# PCB_for_Car.net
KiCad netlist of a schematic drawn in EAGLE
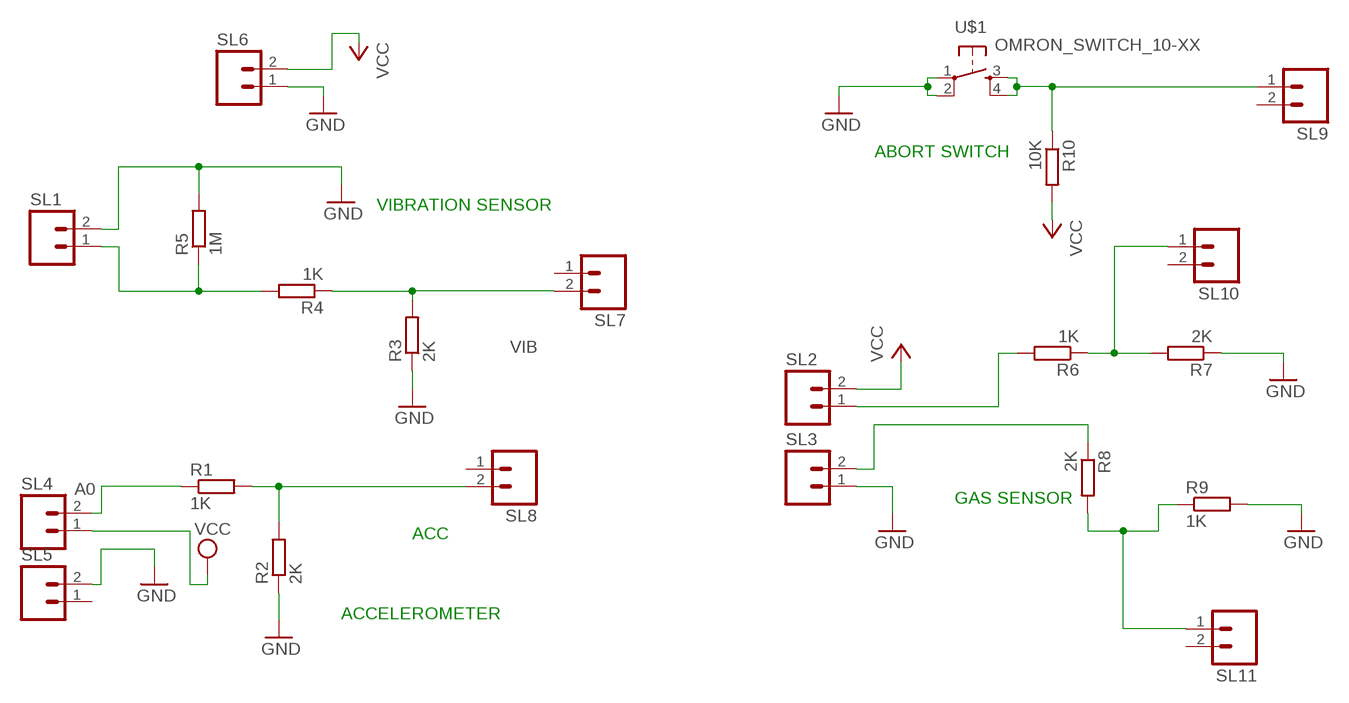
[diagram p0: schematic, sheet 1]

(export (version "E")
  (design (tool "Eeschema 10.0.6"))
  (components
    (comp (ref "R1")
      (value "1K")
      (footprint "eagle-import:0204_7")
      (libsource (lib "eagle-import") (part "R-EU_0204/7"))
    )
    (comp (ref "R2")
      (value "2K")
      (footprint "eagle-import:0204_7")
      (libsource (lib "eagle-import") (part "R-EU_0204/7"))
    )
    (comp (ref "R3")
      (value "2K")
      (footprint "eagle-import:0204_7")
      (libsource (lib "eagle-import") (part "R-EU_0204/7"))
    )
    (comp (ref "R4")
      (value "1K")
      (footprint "eagle-import:0204_7")
      (libsource (lib "eagle-import") (part "R-EU_0204/7"))
    )
    (comp (ref "R5")
      (value "1M")
      (footprint "eagle-import:0204_7")
      (libsource (lib "eagle-import") (part "R-EU_0204/7"))
    )
    (comp (ref "R6")
      (value "1K")
      (footprint "eagle-import:0204_7")
      (libsource (lib "eagle-import") (part "R-EU_0204/7"))
    )
    (comp (ref "R7")
      (value "2K")
      (footprint "eagle-import:0204_7")
      (libsource (lib "eagle-import") (part "R-EU_0204/7"))
    )
    (comp (ref "R8")
      (value "2K")
      (footprint "eagle-import:0204_7")
      (libsource (lib "eagle-import") (part "R-EU_0204/7"))
    )
    (comp (ref "R9")
      (value "1K")
      (footprint "eagle-import:0204_7")
      (libsource (lib "eagle-import") (part "R-EU_0204/7"))
    )
    (comp (ref "R10")
      (value "10K")
      (footprint "eagle-import:0204_7")
      (libsource (lib "eagle-import") (part "R-EU_0204/7"))
    )
    (comp (ref "SL1")
      (value "M02")
      (footprint "eagle-import:02P")
      (libsource (lib "eagle-import") (part "M02"))
    )
    (comp (ref "SL2")
      (value "M02")
      (footprint "eagle-import:02P")
      (libsource (lib "eagle-import") (part "M02"))
    )
    (comp (ref "SL3")
      (value "M02")
      (footprint "eagle-import:02P")
      (libsource (lib "eagle-import") (part "M02"))
    )
    (comp (ref "SL4")
      (value "M02")
      (footprint "eagle-import:02P")
      (libsource (lib "eagle-import") (part "M02"))
    )
    (comp (ref "SL5")
      (value "M02")
      (footprint "eagle-import:02P")
      (libsource (lib "eagle-import") (part "M02"))
    )
    (comp (ref "SL6")
      (value "M02")
      (footprint "eagle-import:02P")
      (libsource (lib "eagle-import") (part "M02"))
    )
    (comp (ref "SL7")
      (value "M02")
      (footprint "eagle-import:02P")
      (libsource (lib "eagle-import") (part "M02"))
    )
    (comp (ref "SL8")
      (value "M02")
      (footprint "eagle-import:02P")
      (libsource (lib "eagle-import") (part "M02"))
    )
    (comp (ref "SL9")
      (value "M02")
      (footprint "eagle-import:02P")
      (libsource (lib "eagle-import") (part "M02"))
    )
    (comp (ref "SL10")
      (value "M02")
      (footprint "eagle-import:02P")
      (libsource (lib "eagle-import") (part "M02"))
    )
    (comp (ref "SL11")
      (value "M02")
      (footprint "eagle-import:02P")
      (libsource (lib "eagle-import") (part "M02"))
    )
    (comp (ref "U$1")
      (value "OMRON_SWITCH_10-XX")
      (footprint "eagle-import:B3F-10XX")
      (libsource (lib "eagle-import") (part "OMRON_SWITCH_10-XX"))
    )
  )
  (nets
    (net (code "1") (name "/A0") (class "Default")
      (node (ref "R1") (pin "1") (pinfunction "1_1") (pintype "passive"))
      (node (ref "SL4") (pin "2") (pinfunction "2_2") (pintype "passive"))
    )
    (net (code "2") (name "GND") (class "Default")
      (node (ref "R2") (pin "1") (pinfunction "1_1") (pintype "passive"))
      (node (ref "R3") (pin "1") (pinfunction "1_1") (pintype "passive"))
      (node (ref "R5") (pin "2") (pinfunction "2_2") (pintype "passive"))
      (node (ref "R7") (pin "1") (pinfunction "1_1") (pintype "passive"))
      (node (ref "R9") (pin "2") (pinfunction "2_2") (pintype "passive"))
      (node (ref "SL1") (pin "2") (pinfunction "2_2") (pintype "passive"))
      (node (ref "SL3") (pin "1") (pinfunction "1_1") (pintype "passive"))
      (node (ref "SL5") (pin "2") (pinfunction "2_2") (pintype "passive"))
      (node (ref "SL6") (pin "1") (pinfunction "1_1") (pintype "passive"))
      (node (ref "U$1") (pin "1") (pinfunction "P_1") (pintype "passive"))
      (node (ref "U$1") (pin "2") (pinfunction "P1_2") (pintype "passive"))
    )
    (net (code "3") (name "Net-(R1-Pad2)") (class "Default")
      (node (ref "R1") (pin "2") (pinfunction "2_2") (pintype "passive"))
      (node (ref "R2") (pin "2") (pinfunction "2_2") (pintype "passive"))
      (node (ref "SL8") (pin "2") (pinfunction "2_2") (pintype "passive"))
    )
    (net (code "4") (name "Net-(R3-Pad2)") (class "Default")
      (node (ref "R3") (pin "2") (pinfunction "2_2") (pintype "passive"))
      (node (ref "R4") (pin "1") (pinfunction "1_1") (pintype "passive"))
      (node (ref "SL7") (pin "2") (pinfunction "2_2") (pintype "passive"))
    )
    (net (code "5") (name "Net-(R4-Pad2)") (class "Default")
      (node (ref "R4") (pin "2") (pinfunction "2_2") (pintype "passive"))
      (node (ref "R5") (pin "1") (pinfunction "1_1") (pintype "passive"))
      (node (ref "SL1") (pin "1") (pinfunction "1_1") (pintype "passive"))
    )
    (net (code "6") (name "Net-(R6-Pad1)") (class "Default")
      (node (ref "R6") (pin "1") (pinfunction "1_1") (pintype "passive"))
      (node (ref "R7") (pin "2") (pinfunction "2_2") (pintype "passive"))
      (node (ref "SL10") (pin "1") (pinfunction "1_1") (pintype "passive"))
    )
    (net (code "7") (name "Net-(R6-Pad2)") (class "Default")
      (node (ref "R6") (pin "2") (pinfunction "2_2") (pintype "passive"))
      (node (ref "SL2") (pin "1") (pinfunction "1_1") (pintype "passive"))
    )
    (net (code "8") (name "Net-(R8-Pad1)") (class "Default")
      (node (ref "R8") (pin "1") (pinfunction "1_1") (pintype "passive"))
      (node (ref "SL3") (pin "2") (pinfunction "2_2") (pintype "passive"))
    )
    (net (code "9") (name "Net-(R8-Pad2)") (class "Default")
      (node (ref "R8") (pin "2") (pinfunction "2_2") (pintype "passive"))
      (node (ref "R9") (pin "1") (pinfunction "1_1") (pintype "passive"))
      (node (ref "SL11") (pin "1") (pinfunction "1_1") (pintype "passive"))
    )
    (net (code "10") (name "Net-(U$1-S)") (class "Default")
      (node (ref "R10") (pin "1") (pinfunction "1_1") (pintype "passive"))
      (node (ref "SL9") (pin "1") (pinfunction "1_1") (pintype "passive"))
      (node (ref "U$1") (pin "3") (pinfunction "S_3") (pintype "passive"))
      (node (ref "U$1") (pin "4") (pinfunction "S1_4") (pintype "passive"))
    )
    (net (code "11") (name "VCC") (class "Default")
      (node (ref "R10") (pin "2") (pinfunction "2_2") (pintype "passive"))
      (node (ref "SL2") (pin "2") (pinfunction "2_2") (pintype "passive"))
      (node (ref "SL4") (pin "1") (pinfunction "1_1") (pintype "passive"))
      (node (ref "SL6") (pin "2") (pinfunction "2_2") (pintype "passive"))
    )
    (net (code "12") (name "unconnected-(SL5-Pad1)") (class "Default")
      (node (ref "SL5") (pin "1") (pinfunction "1_1") (pintype "passive"))
    )
    (net (code "13") (name "unconnected-(SL7-Pad1)") (class "Default")
      (node (ref "SL7") (pin "1") (pinfunction "1_1") (pintype "passive"))
    )
    (net (code "14") (name "unconnected-(SL8-Pad1)") (class "Default")
      (node (ref "SL8") (pin "1") (pinfunction "1_1") (pintype "passive"))
    )
    (net (code "15") (name "unconnected-(SL9-Pad2)") (class "Default")
      (node (ref "SL9") (pin "2") (pinfunction "2_2") (pintype "passive"))
    )
    (net (code "16") (name "unconnected-(SL10-Pad2)") (class "Default")
      (node (ref "SL10") (pin "2") (pinfunction "2_2") (pintype "passive"))
    )
    (net (code "17") (name "unconnected-(SL11-Pad2)") (class "Default")
      (node (ref "SL11") (pin "2") (pinfunction "2_2") (pintype "passive"))
    )
  )
)
